# flags.net
KiCad netlist of a schematic drawn in EAGLE
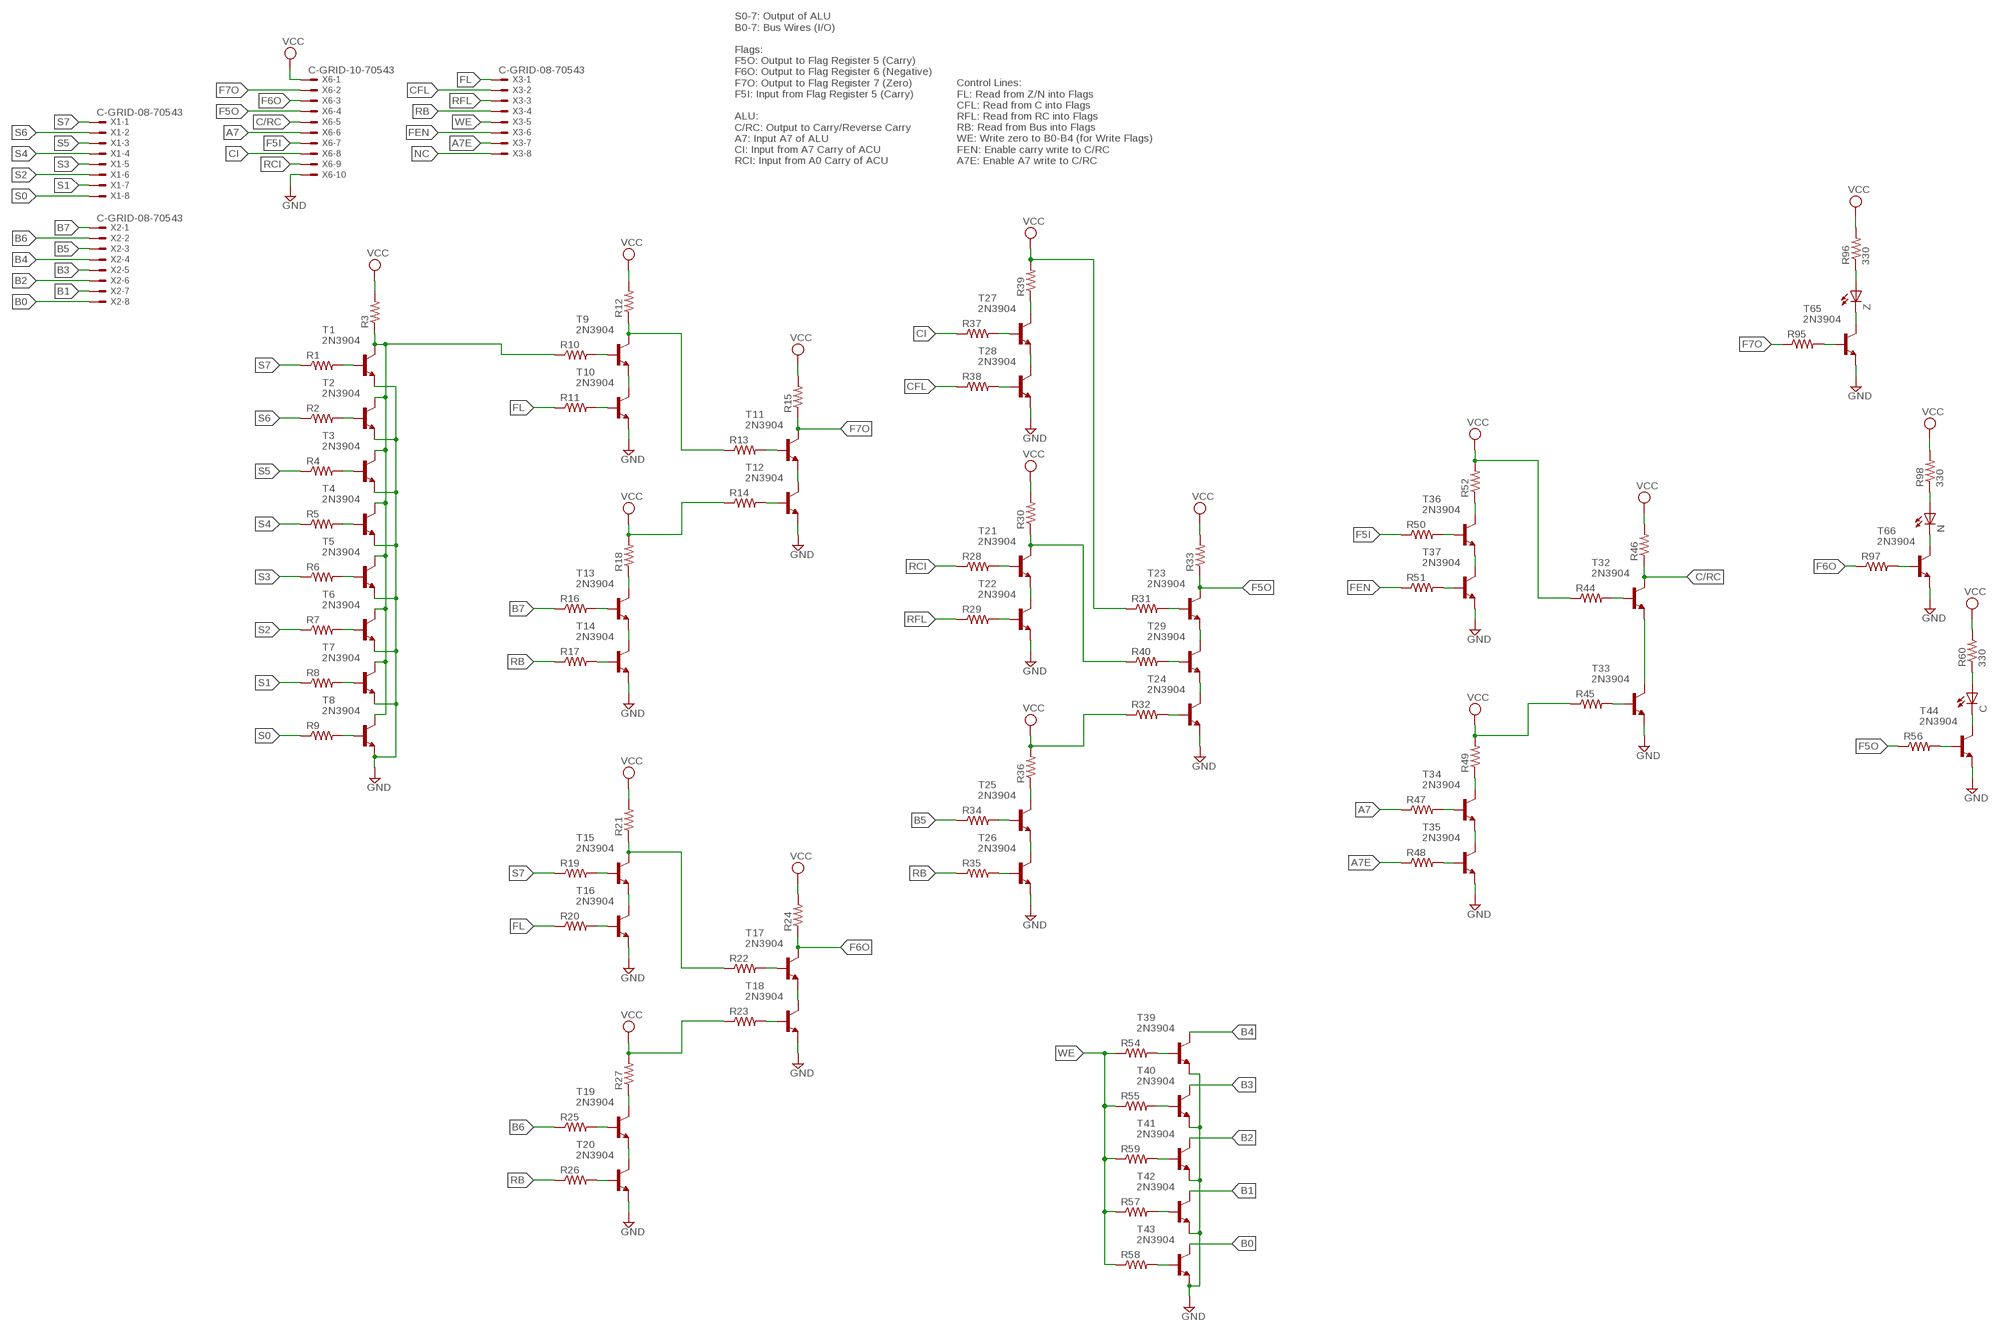
[diagram p0: schematic, sheet 1]

(export (version "E")
  (design (tool "Eeschema 10.0.6"))
  (components
    (comp (ref "C")
      (value "LED5MM")
      (footprint "eagle-import:LED5MM")
      (libsource (lib "eagle-import") (part "LED5MM"))
    )
    (comp (ref "N")
      (value "LED5MM")
      (footprint "eagle-import:LED5MM")
      (libsource (lib "eagle-import") (part "LED5MM"))
    )
    (comp (ref "R1")
      (value "R-US_0309/10")
      (footprint "eagle-import:0309_10")
      (libsource (lib "eagle-import") (part "R-US_0309/10"))
    )
    (comp (ref "R2")
      (value "R-US_0309/10")
      (footprint "eagle-import:0309_10")
      (libsource (lib "eagle-import") (part "R-US_0309/10"))
    )
    (comp (ref "R3")
      (value "R-US_0309/10")
      (footprint "eagle-import:0309_10")
      (libsource (lib "eagle-import") (part "R-US_0309/10"))
    )
    (comp (ref "R4")
      (value "R-US_0309/10")
      (footprint "eagle-import:0309_10")
      (libsource (lib "eagle-import") (part "R-US_0309/10"))
    )
    (comp (ref "R5")
      (value "R-US_0309/10")
      (footprint "eagle-import:0309_10")
      (libsource (lib "eagle-import") (part "R-US_0309/10"))
    )
    (comp (ref "R6")
      (value "R-US_0309/10")
      (footprint "eagle-import:0309_10")
      (libsource (lib "eagle-import") (part "R-US_0309/10"))
    )
    (comp (ref "R7")
      (value "R-US_0309/10")
      (footprint "eagle-import:0309_10")
      (libsource (lib "eagle-import") (part "R-US_0309/10"))
    )
    (comp (ref "R8")
      (value "R-US_0309/10")
      (footprint "eagle-import:0309_10")
      (libsource (lib "eagle-import") (part "R-US_0309/10"))
    )
    (comp (ref "R9")
      (value "R-US_0309/10")
      (footprint "eagle-import:0309_10")
      (libsource (lib "eagle-import") (part "R-US_0309/10"))
    )
    (comp (ref "R10")
      (value "R-US_0309/10")
      (footprint "eagle-import:0309_10")
      (libsource (lib "eagle-import") (part "R-US_0309/10"))
    )
    (comp (ref "R11")
      (value "R-US_0309/10")
      (footprint "eagle-import:0309_10")
      (libsource (lib "eagle-import") (part "R-US_0309/10"))
    )
    (comp (ref "R12")
      (value "R-US_0309/10")
      (footprint "eagle-import:0309_10")
      (libsource (lib "eagle-import") (part "R-US_0309/10"))
    )
    (comp (ref "R13")
      (value "R-US_0309/10")
      (footprint "eagle-import:0309_10")
      (libsource (lib "eagle-import") (part "R-US_0309/10"))
    )
    (comp (ref "R14")
      (value "R-US_0309/10")
      (footprint "eagle-import:0309_10")
      (libsource (lib "eagle-import") (part "R-US_0309/10"))
    )
    (comp (ref "R15")
      (value "R-US_0309/10")
      (footprint "eagle-import:0309_10")
      (libsource (lib "eagle-import") (part "R-US_0309/10"))
    )
    (comp (ref "R16")
      (value "R-US_0309/10")
      (footprint "eagle-import:0309_10")
      (libsource (lib "eagle-import") (part "R-US_0309/10"))
    )
    (comp (ref "R17")
      (value "R-US_0309/10")
      (footprint "eagle-import:0309_10")
      (libsource (lib "eagle-import") (part "R-US_0309/10"))
    )
    (comp (ref "R18")
      (value "R-US_0309/10")
      (footprint "eagle-import:0309_10")
      (libsource (lib "eagle-import") (part "R-US_0309/10"))
    )
    (comp (ref "R19")
      (value "R-US_0309/10")
      (footprint "eagle-import:0309_10")
      (libsource (lib "eagle-import") (part "R-US_0309/10"))
    )
    (comp (ref "R20")
      (value "R-US_0309/10")
      (footprint "eagle-import:0309_10")
      (libsource (lib "eagle-import") (part "R-US_0309/10"))
    )
    (comp (ref "R21")
      (value "R-US_0309/10")
      (footprint "eagle-import:0309_10")
      (libsource (lib "eagle-import") (part "R-US_0309/10"))
    )
    (comp (ref "R22")
      (value "R-US_0309/10")
      (footprint "eagle-import:0309_10")
      (libsource (lib "eagle-import") (part "R-US_0309/10"))
    )
    (comp (ref "R23")
      (value "R-US_0309/10")
      (footprint "eagle-import:0309_10")
      (libsource (lib "eagle-import") (part "R-US_0309/10"))
    )
    (comp (ref "R24")
      (value "R-US_0309/10")
      (footprint "eagle-import:0309_10")
      (libsource (lib "eagle-import") (part "R-US_0309/10"))
    )
    (comp (ref "R25")
      (value "R-US_0309/10")
      (footprint "eagle-import:0309_10")
      (libsource (lib "eagle-import") (part "R-US_0309/10"))
    )
    (comp (ref "R26")
      (value "R-US_0309/10")
      (footprint "eagle-import:0309_10")
      (libsource (lib "eagle-import") (part "R-US_0309/10"))
    )
    (comp (ref "R27")
      (value "R-US_0309/10")
      (footprint "eagle-import:0309_10")
      (libsource (lib "eagle-import") (part "R-US_0309/10"))
    )
    (comp (ref "R28")
      (value "R-US_0309/10")
      (footprint "eagle-import:0309_10")
      (libsource (lib "eagle-import") (part "R-US_0309/10"))
    )
    (comp (ref "R29")
      (value "R-US_0309/10")
      (footprint "eagle-import:0309_10")
      (libsource (lib "eagle-import") (part "R-US_0309/10"))
    )
    (comp (ref "R30")
      (value "R-US_0309/10")
      (footprint "eagle-import:0309_10")
      (libsource (lib "eagle-import") (part "R-US_0309/10"))
    )
    (comp (ref "R31")
      (value "R-US_0309/10")
      (footprint "eagle-import:0309_10")
      (libsource (lib "eagle-import") (part "R-US_0309/10"))
    )
    (comp (ref "R32")
      (value "R-US_0309/10")
      (footprint "eagle-import:0309_10")
      (libsource (lib "eagle-import") (part "R-US_0309/10"))
    )
    (comp (ref "R33")
      (value "R-US_0309/10")
      (footprint "eagle-import:0309_10")
      (libsource (lib "eagle-import") (part "R-US_0309/10"))
    )
    (comp (ref "R34")
      (value "R-US_0309/10")
      (footprint "eagle-import:0309_10")
      (libsource (lib "eagle-import") (part "R-US_0309/10"))
    )
    (comp (ref "R35")
      (value "R-US_0309/10")
      (footprint "eagle-import:0309_10")
      (libsource (lib "eagle-import") (part "R-US_0309/10"))
    )
    (comp (ref "R36")
      (value "R-US_0309/10")
      (footprint "eagle-import:0309_10")
      (libsource (lib "eagle-import") (part "R-US_0309/10"))
    )
    (comp (ref "R37")
      (value "R-US_0309/10")
      (footprint "eagle-import:0309_10")
      (libsource (lib "eagle-import") (part "R-US_0309/10"))
    )
    (comp (ref "R38")
      (value "R-US_0309/10")
      (footprint "eagle-import:0309_10")
      (libsource (lib "eagle-import") (part "R-US_0309/10"))
    )
    (comp (ref "R39")
      (value "R-US_0309/10")
      (footprint "eagle-import:0309_10")
      (libsource (lib "eagle-import") (part "R-US_0309/10"))
    )
    (comp (ref "R40")
      (value "R-US_0309/10")
      (footprint "eagle-import:0309_10")
      (libsource (lib "eagle-import") (part "R-US_0309/10"))
    )
    (comp (ref "R44")
      (value "R-US_0309/10")
      (footprint "eagle-import:0309_10")
      (libsource (lib "eagle-import") (part "R-US_0309/10"))
    )
    (comp (ref "R45")
      (value "R-US_0309/10")
      (footprint "eagle-import:0309_10")
      (libsource (lib "eagle-import") (part "R-US_0309/10"))
    )
    (comp (ref "R46")
      (value "R-US_0309/10")
      (footprint "eagle-import:0309_10")
      (libsource (lib "eagle-import") (part "R-US_0309/10"))
    )
    (comp (ref "R47")
      (value "R-US_0309/10")
      (footprint "eagle-import:0309_10")
      (libsource (lib "eagle-import") (part "R-US_0309/10"))
    )
    (comp (ref "R48")
      (value "R-US_0309/10")
      (footprint "eagle-import:0309_10")
      (libsource (lib "eagle-import") (part "R-US_0309/10"))
    )
    (comp (ref "R49")
      (value "R-US_0309/10")
      (footprint "eagle-import:0309_10")
      (libsource (lib "eagle-import") (part "R-US_0309/10"))
    )
    (comp (ref "R50")
      (value "R-US_0309/10")
      (footprint "eagle-import:0309_10")
      (libsource (lib "eagle-import") (part "R-US_0309/10"))
    )
    (comp (ref "R51")
      (value "R-US_0309/10")
      (footprint "eagle-import:0309_10")
      (libsource (lib "eagle-import") (part "R-US_0309/10"))
    )
    (comp (ref "R52")
      (value "R-US_0309/10")
      (footprint "eagle-import:0309_10")
      (libsource (lib "eagle-import") (part "R-US_0309/10"))
    )
    (comp (ref "R54")
      (value "R-US_0309/10")
      (footprint "eagle-import:0309_10")
      (libsource (lib "eagle-import") (part "R-US_0309/10"))
    )
    (comp (ref "R55")
      (value "R-US_0309/10")
      (footprint "eagle-import:0309_10")
      (libsource (lib "eagle-import") (part "R-US_0309/10"))
    )
    (comp (ref "R56")
      (value "R-US_0309/10")
      (footprint "eagle-import:0309_10")
      (libsource (lib "eagle-import") (part "R-US_0309/10"))
    )
    (comp (ref "R57")
      (value "R-US_0309/10")
      (footprint "eagle-import:0309_10")
      (libsource (lib "eagle-import") (part "R-US_0309/10"))
    )
    (comp (ref "R58")
      (value "R-US_0309/10")
      (footprint "eagle-import:0309_10")
      (libsource (lib "eagle-import") (part "R-US_0309/10"))
    )
    (comp (ref "R59")
      (value "R-US_0309/10")
      (footprint "eagle-import:0309_10")
      (libsource (lib "eagle-import") (part "R-US_0309/10"))
    )
    (comp (ref "R60")
      (value "330")
      (footprint "eagle-import:0309_10")
      (libsource (lib "eagle-import") (part "R-US_0309/10"))
    )
    (comp (ref "R95")
      (value "R-US_0309/10")
      (footprint "eagle-import:0309_10")
      (libsource (lib "eagle-import") (part "R-US_0309/10"))
    )
    (comp (ref "R96")
      (value "330")
      (footprint "eagle-import:0309_10")
      (libsource (lib "eagle-import") (part "R-US_0309/10"))
    )
    (comp (ref "R97")
      (value "R-US_0309/10")
      (footprint "eagle-import:0309_10")
      (libsource (lib "eagle-import") (part "R-US_0309/10"))
    )
    (comp (ref "R98")
      (value "330")
      (footprint "eagle-import:0309_10")
      (libsource (lib "eagle-import") (part "R-US_0309/10"))
    )
    (comp (ref "T1")
      (value "2N3904")
      (footprint "eagle-import:TO92")
      (libsource (lib "eagle-import") (part "2N3904"))
    )
    (comp (ref "T2")
      (value "2N3904")
      (footprint "eagle-import:TO92")
      (libsource (lib "eagle-import") (part "2N3904"))
    )
    (comp (ref "T3")
      (value "2N3904")
      (footprint "eagle-import:TO92")
      (libsource (lib "eagle-import") (part "2N3904"))
    )
    (comp (ref "T4")
      (value "2N3904")
      (footprint "eagle-import:TO92")
      (libsource (lib "eagle-import") (part "2N3904"))
    )
    (comp (ref "T5")
      (value "2N3904")
      (footprint "eagle-import:TO92")
      (libsource (lib "eagle-import") (part "2N3904"))
    )
    (comp (ref "T6")
      (value "2N3904")
      (footprint "eagle-import:TO92")
      (libsource (lib "eagle-import") (part "2N3904"))
    )
    (comp (ref "T7")
      (value "2N3904")
      (footprint "eagle-import:TO92")
      (libsource (lib "eagle-import") (part "2N3904"))
    )
    (comp (ref "T8")
      (value "2N3904")
      (footprint "eagle-import:TO92")
      (libsource (lib "eagle-import") (part "2N3904"))
    )
    (comp (ref "T9")
      (value "2N3904")
      (footprint "eagle-import:TO92")
      (libsource (lib "eagle-import") (part "2N3904"))
    )
    (comp (ref "T10")
      (value "2N3904")
      (footprint "eagle-import:TO92")
      (libsource (lib "eagle-import") (part "2N3904"))
    )
    (comp (ref "T11")
      (value "2N3904")
      (footprint "eagle-import:TO92")
      (libsource (lib "eagle-import") (part "2N3904"))
    )
    (comp (ref "T12")
      (value "2N3904")
      (footprint "eagle-import:TO92")
      (libsource (lib "eagle-import") (part "2N3904"))
    )
    (comp (ref "T13")
      (value "2N3904")
      (footprint "eagle-import:TO92")
      (libsource (lib "eagle-import") (part "2N3904"))
    )
    (comp (ref "T14")
      (value "2N3904")
      (footprint "eagle-import:TO92")
      (libsource (lib "eagle-import") (part "2N3904"))
    )
    (comp (ref "T15")
      (value "2N3904")
      (footprint "eagle-import:TO92")
      (libsource (lib "eagle-import") (part "2N3904"))
    )
    (comp (ref "T16")
      (value "2N3904")
      (footprint "eagle-import:TO92")
      (libsource (lib "eagle-import") (part "2N3904"))
    )
    (comp (ref "T17")
      (value "2N3904")
      (footprint "eagle-import:TO92")
      (libsource (lib "eagle-import") (part "2N3904"))
    )
    (comp (ref "T18")
      (value "2N3904")
      (footprint "eagle-import:TO92")
      (libsource (lib "eagle-import") (part "2N3904"))
    )
    (comp (ref "T19")
      (value "2N3904")
      (footprint "eagle-import:TO92")
      (libsource (lib "eagle-import") (part "2N3904"))
    )
    (comp (ref "T20")
      (value "2N3904")
      (footprint "eagle-import:TO92")
      (libsource (lib "eagle-import") (part "2N3904"))
    )
    (comp (ref "T21")
      (value "2N3904")
      (footprint "eagle-import:TO92")
      (libsource (lib "eagle-import") (part "2N3904"))
    )
    (comp (ref "T22")
      (value "2N3904")
      (footprint "eagle-import:TO92")
      (libsource (lib "eagle-import") (part "2N3904"))
    )
    (comp (ref "T23")
      (value "2N3904")
      (footprint "eagle-import:TO92")
      (libsource (lib "eagle-import") (part "2N3904"))
    )
    (comp (ref "T24")
      (value "2N3904")
      (footprint "eagle-import:TO92")
      (libsource (lib "eagle-import") (part "2N3904"))
    )
    (comp (ref "T25")
      (value "2N3904")
      (footprint "eagle-import:TO92")
      (libsource (lib "eagle-import") (part "2N3904"))
    )
    (comp (ref "T26")
      (value "2N3904")
      (footprint "eagle-import:TO92")
      (libsource (lib "eagle-import") (part "2N3904"))
    )
    (comp (ref "T27")
      (value "2N3904")
      (footprint "eagle-import:TO92")
      (libsource (lib "eagle-import") (part "2N3904"))
    )
    (comp (ref "T28")
      (value "2N3904")
      (footprint "eagle-import:TO92")
      (libsource (lib "eagle-import") (part "2N3904"))
    )
    (comp (ref "T29")
      (value "2N3904")
      (footprint "eagle-import:TO92")
      (libsource (lib "eagle-import") (part "2N3904"))
    )
    (comp (ref "T32")
      (value "2N3904")
      (footprint "eagle-import:TO92")
      (libsource (lib "eagle-import") (part "2N3904"))
    )
    (comp (ref "T33")
      (value "2N3904")
      (footprint "eagle-import:TO92")
      (libsource (lib "eagle-import") (part "2N3904"))
    )
    (comp (ref "T34")
      (value "2N3904")
      (footprint "eagle-import:TO92")
      (libsource (lib "eagle-import") (part "2N3904"))
    )
    (comp (ref "T35")
      (value "2N3904")
      (footprint "eagle-import:TO92")
      (libsource (lib "eagle-import") (part "2N3904"))
    )
    (comp (ref "T36")
      (value "2N3904")
      (footprint "eagle-import:TO92")
      (libsource (lib "eagle-import") (part "2N3904"))
    )
    (comp (ref "T37")
      (value "2N3904")
      (footprint "eagle-import:TO92")
      (libsource (lib "eagle-import") (part "2N3904"))
    )
    (comp (ref "T39")
      (value "2N3904")
      (footprint "eagle-import:TO92")
      (libsource (lib "eagle-import") (part "2N3904"))
    )
    (comp (ref "T40")
      (value "2N3904")
      (footprint "eagle-import:TO92")
      (libsource (lib "eagle-import") (part "2N3904"))
    )
    (comp (ref "T41")
      (value "2N3904")
      (footprint "eagle-import:TO92")
      (libsource (lib "eagle-import") (part "2N3904"))
    )
    (comp (ref "T42")
      (value "2N3904")
      (footprint "eagle-import:TO92")
      (libsource (lib "eagle-import") (part "2N3904"))
    )
    (comp (ref "T43")
      (value "2N3904")
      (footprint "eagle-import:TO92")
      (libsource (lib "eagle-import") (part "2N3904"))
    )
    (comp (ref "T44")
      (value "2N3904")
      (footprint "eagle-import:TO92")
      (libsource (lib "eagle-import") (part "2N3904"))
    )
    (comp (ref "T65")
      (value "2N3904")
      (footprint "eagle-import:TO92")
      (libsource (lib "eagle-import") (part "2N3904"))
    )
    (comp (ref "T66")
      (value "2N3904")
      (footprint "eagle-import:TO92")
      (libsource (lib "eagle-import") (part "2N3904"))
    )
    (comp (ref "X1")
      (value "C-GRID-08-70543")
      (footprint "eagle-import:70543-08")
      (fields (field (name "MF") "MOLEX"))
      (libsource (lib "eagle-import") (part "C-GRID-08-70543"))
    )
    (comp (ref "X2")
      (value "C-GRID-08-70543")
      (footprint "eagle-import:70543-08")
      (fields (field (name "MF") "MOLEX"))
      (libsource (lib "eagle-import") (part "C-GRID-08-70543"))
    )
    (comp (ref "X3")
      (value "C-GRID-08-70543")
      (footprint "eagle-import:70543-08")
      (fields (field (name "MF") "MOLEX"))
      (libsource (lib "eagle-import") (part "C-GRID-08-70543"))
    )
    (comp (ref "X6")
      (value "C-GRID-10-70543")
      (footprint "eagle-import:70543-10")
      (fields (field (name "MF") "MOLEX"))
      (libsource (lib "eagle-import") (part "C-GRID-10-70543"))
    )
    (comp (ref "Z")
      (value "LED5MM")
      (footprint "eagle-import:LED5MM")
      (libsource (lib "eagle-import") (part "LED5MM"))
    )
  )
  (nets
    (net (code "1") (name "A7") (class "Default")
      (node (ref "R47") (pin "1") (pinfunction "1_1") (pintype "passive"))
      (node (ref "X6") (pin "6") (pinfunction "S_6") (pintype "passive"))
    )
    (net (code "2") (name "A7E") (class "Default")
      (node (ref "R48") (pin "1") (pinfunction "1_1") (pintype "passive"))
      (node (ref "X3") (pin "7") (pinfunction "S_7") (pintype "passive"))
    )
    (net (code "3") (name "B0") (class "Default")
      (node (ref "T43") (pin "1") (pinfunction "C_1") (pintype "passive"))
      (node (ref "X2") (pin "8") (pinfunction "S_8") (pintype "passive"))
    )
    (net (code "4") (name "B1") (class "Default")
      (node (ref "T42") (pin "1") (pinfunction "C_1") (pintype "passive"))
      (node (ref "X2") (pin "7") (pinfunction "S_7") (pintype "passive"))
    )
    (net (code "5") (name "B2") (class "Default")
      (node (ref "T41") (pin "1") (pinfunction "C_1") (pintype "passive"))
      (node (ref "X2") (pin "6") (pinfunction "S_6") (pintype "passive"))
    )
    (net (code "6") (name "B3") (class "Default")
      (node (ref "T40") (pin "1") (pinfunction "C_1") (pintype "passive"))
      (node (ref "X2") (pin "5") (pinfunction "S_5") (pintype "passive"))
    )
    (net (code "7") (name "B4") (class "Default")
      (node (ref "T39") (pin "1") (pinfunction "C_1") (pintype "passive"))
      (node (ref "X2") (pin "4") (pinfunction "S_4") (pintype "passive"))
    )
    (net (code "8") (name "B5") (class "Default")
      (node (ref "R34") (pin "1") (pinfunction "1_1") (pintype "passive"))
      (node (ref "X2") (pin "3") (pinfunction "S_3") (pintype "passive"))
    )
    (net (code "9") (name "B6") (class "Default")
      (node (ref "R25") (pin "1") (pinfunction "1_1") (pintype "passive"))
      (node (ref "X2") (pin "2") (pinfunction "S_2") (pintype "passive"))
    )
    (net (code "10") (name "B7") (class "Default")
      (node (ref "R16") (pin "1") (pinfunction "1_1") (pintype "passive"))
      (node (ref "X2") (pin "1") (pinfunction "S_1") (pintype "passive"))
    )
    (net (code "11") (name "CFL") (class "Default")
      (node (ref "R38") (pin "1") (pinfunction "1_1") (pintype "passive"))
      (node (ref "X3") (pin "2") (pinfunction "S_2") (pintype "passive"))
    )
    (net (code "12") (name "CI") (class "Default")
      (node (ref "R37") (pin "1") (pinfunction "1_1") (pintype "passive"))
      (node (ref "X6") (pin "8") (pinfunction "S_8") (pintype "passive"))
    )
    (net (code "13") (name "C{slash}RC") (class "Default")
      (node (ref "R46") (pin "1") (pinfunction "1_1") (pintype "passive"))
      (node (ref "T32") (pin "1") (pinfunction "C_1") (pintype "passive"))
      (node (ref "X6") (pin "5") (pinfunction "S_5") (pintype "passive"))
    )
    (net (code "14") (name "F5I") (class "Default")
      (node (ref "R50") (pin "1") (pinfunction "1_1") (pintype "passive"))
      (node (ref "X6") (pin "7") (pinfunction "S_7") (pintype "passive"))
    )
    (net (code "15") (name "F5O") (class "Default")
      (node (ref "R33") (pin "1") (pinfunction "1_1") (pintype "passive"))
      (node (ref "R56") (pin "1") (pinfunction "1_1") (pintype "passive"))
      (node (ref "T23") (pin "1") (pinfunction "C_1") (pintype "passive"))
      (node (ref "X6") (pin "4") (pinfunction "S_4") (pintype "passive"))
    )
    (net (code "16") (name "F6O") (class "Default")
      (node (ref "R24") (pin "1") (pinfunction "1_1") (pintype "passive"))
      (node (ref "R97") (pin "1") (pinfunction "1_1") (pintype "passive"))
      (node (ref "T17") (pin "1") (pinfunction "C_1") (pintype "passive"))
      (node (ref "X6") (pin "3") (pinfunction "S_3") (pintype "passive"))
    )
    (net (code "17") (name "F7O") (class "Default")
      (node (ref "R15") (pin "1") (pinfunction "1_1") (pintype "passive"))
      (node (ref "R95") (pin "1") (pinfunction "1_1") (pintype "passive"))
      (node (ref "T11") (pin "1") (pinfunction "C_1") (pintype "passive"))
      (node (ref "X6") (pin "2") (pinfunction "S_2") (pintype "passive"))
    )
    (net (code "18") (name "FEN") (class "Default")
      (node (ref "R51") (pin "1") (pinfunction "1_1") (pintype "passive"))
      (node (ref "X3") (pin "6") (pinfunction "S_6") (pintype "passive"))
    )
    (net (code "19") (name "FL") (class "Default")
      (node (ref "R11") (pin "1") (pinfunction "1_1") (pintype "passive"))
      (node (ref "R20") (pin "1") (pinfunction "1_1") (pintype "passive"))
      (node (ref "X3") (pin "1") (pinfunction "S_1") (pintype "passive"))
    )
    (net (code "20") (name "GND") (class "Default")
      (node (ref "T1") (pin "3") (pinfunction "E_3") (pintype "passive"))
      (node (ref "T10") (pin "3") (pinfunction "E_3") (pintype "passive"))
      (node (ref "T12") (pin "3") (pinfunction "E_3") (pintype "passive"))
      (node (ref "T14") (pin "3") (pinfunction "E_3") (pintype "passive"))
      (node (ref "T16") (pin "3") (pinfunction "E_3") (pintype "passive"))
      (node (ref "T18") (pin "3") (pinfunction "E_3") (pintype "passive"))
      (node (ref "T2") (pin "3") (pinfunction "E_3") (pintype "passive"))
      (node (ref "T20") (pin "3") (pinfunction "E_3") (pintype "passive"))
      (node (ref "T22") (pin "3") (pinfunction "E_3") (pintype "passive"))
      (node (ref "T24") (pin "3") (pinfunction "E_3") (pintype "passive"))
      (node (ref "T26") (pin "3") (pinfunction "E_3") (pintype "passive"))
      (node (ref "T28") (pin "3") (pinfunction "E_3") (pintype "passive"))
      (node (ref "T3") (pin "3") (pinfunction "E_3") (pintype "passive"))
      (node (ref "T33") (pin "3") (pinfunction "E_3") (pintype "passive"))
      (node (ref "T35") (pin "3") (pinfunction "E_3") (pintype "passive"))
      (node (ref "T37") (pin "3") (pinfunction "E_3") (pintype "passive"))
      (node (ref "T39") (pin "3") (pinfunction "E_3") (pintype "passive"))
      (node (ref "T4") (pin "3") (pinfunction "E_3") (pintype "passive"))
      (node (ref "T40") (pin "3") (pinfunction "E_3") (pintype "passive"))
      (node (ref "T41") (pin "3") (pinfunction "E_3") (pintype "passive"))
      (node (ref "T42") (pin "3") (pinfunction "E_3") (pintype "passive"))
      (node (ref "T43") (pin "3") (pinfunction "E_3") (pintype "passive"))
      (node (ref "T44") (pin "3") (pinfunction "E_3") (pintype "passive"))
      (node (ref "T5") (pin "3") (pinfunction "E_3") (pintype "passive"))
      (node (ref "T6") (pin "3") (pinfunction "E_3") (pintype "passive"))
      (node (ref "T65") (pin "3") (pinfunction "E_3") (pintype "passive"))
      (node (ref "T66") (pin "3") (pinfunction "E_3") (pintype "passive"))
      (node (ref "T7") (pin "3") (pinfunction "E_3") (pintype "passive"))
      (node (ref "T8") (pin "3") (pinfunction "E_3") (pintype "passive"))
      (node (ref "X6") (pin "10") (pinfunction "S_10") (pintype "passive"))
    )
    (net (code "21") (name "NC") (class "Default")
      (node (ref "X3") (pin "8") (pinfunction "S_8") (pintype "passive"))
    )
    (net (code "22") (name "Net-(C-C)") (class "Default")
      (node (ref "C") (pin "K") (pinfunction "C_K") (pintype "passive"))
      (node (ref "T44") (pin "1") (pinfunction "C_1") (pintype "passive"))
    )
    (net (code "23") (name "Net-(C-PadA)") (class "Default")
      (node (ref "C") (pin "A") (pinfunction "A_A") (pintype "passive"))
      (node (ref "R60") (pin "1") (pinfunction "1_1") (pintype "passive"))
    )
    (net (code "24") (name "Net-(N-C)") (class "Default")
      (node (ref "N") (pin "K") (pinfunction "C_K") (pintype "passive"))
      (node (ref "T66") (pin "1") (pinfunction "C_1") (pintype "passive"))
    )
    (net (code "25") (name "Net-(N-PadA)") (class "Default")
      (node (ref "N") (pin "A") (pinfunction "A_A") (pintype "passive"))
      (node (ref "R98") (pin "1") (pinfunction "1_1") (pintype "passive"))
    )
    (net (code "26") (name "Net-(R96-Pad1)") (class "Default")
      (node (ref "R96") (pin "1") (pinfunction "1_1") (pintype "passive"))
      (node (ref "Z") (pin "A") (pinfunction "A_A") (pintype "passive"))
    )
    (net (code "27") (name "Net-(T1-B)") (class "Default")
      (node (ref "R1") (pin "2") (pinfunction "2_2") (pintype "passive"))
      (node (ref "T1") (pin "2") (pinfunction "B_2") (pintype "passive"))
    )
    (net (code "28") (name "Net-(T1-C)") (class "Default")
      (node (ref "R10") (pin "1") (pinfunction "1_1") (pintype "passive"))
      (node (ref "R3") (pin "1") (pinfunction "1_1") (pintype "passive"))
      (node (ref "T1") (pin "1") (pinfunction "C_1") (pintype "passive"))
      (node (ref "T2") (pin "1") (pinfunction "C_1") (pintype "passive"))
      (node (ref "T3") (pin "1") (pinfunction "C_1") (pintype "passive"))
      (node (ref "T4") (pin "1") (pinfunction "C_1") (pintype "passive"))
      (node (ref "T5") (pin "1") (pinfunction "C_1") (pintype "passive"))
      (node (ref "T6") (pin "1") (pinfunction "C_1") (pintype "passive"))
      (node (ref "T7") (pin "1") (pinfunction "C_1") (pintype "passive"))
      (node (ref "T8") (pin "1") (pinfunction "C_1") (pintype "passive"))
    )
    (net (code "29") (name "Net-(T2-B)") (class "Default")
      (node (ref "R2") (pin "2") (pinfunction "2_2") (pintype "passive"))
      (node (ref "T2") (pin "2") (pinfunction "B_2") (pintype "passive"))
    )
    (net (code "30") (name "Net-(T3-B)") (class "Default")
      (node (ref "R4") (pin "2") (pinfunction "2_2") (pintype "passive"))
      (node (ref "T3") (pin "2") (pinfunction "B_2") (pintype "passive"))
    )
    (net (code "31") (name "Net-(T4-B)") (class "Default")
      (node (ref "R5") (pin "2") (pinfunction "2_2") (pintype "passive"))
      (node (ref "T4") (pin "2") (pinfunction "B_2") (pintype "passive"))
    )
    (net (code "32") (name "Net-(T5-B)") (class "Default")
      (node (ref "R6") (pin "2") (pinfunction "2_2") (pintype "passive"))
      (node (ref "T5") (pin "2") (pinfunction "B_2") (pintype "passive"))
    )
    (net (code "33") (name "Net-(T6-B)") (class "Default")
      (node (ref "R7") (pin "2") (pinfunction "2_2") (pintype "passive"))
      (node (ref "T6") (pin "2") (pinfunction "B_2") (pintype "passive"))
    )
    (net (code "34") (name "Net-(T7-B)") (class "Default")
      (node (ref "R8") (pin "2") (pinfunction "2_2") (pintype "passive"))
      (node (ref "T7") (pin "2") (pinfunction "B_2") (pintype "passive"))
    )
    (net (code "35") (name "Net-(T8-B)") (class "Default")
      (node (ref "R9") (pin "2") (pinfunction "2_2") (pintype "passive"))
      (node (ref "T8") (pin "2") (pinfunction "B_2") (pintype "passive"))
    )
    (net (code "36") (name "Net-(T9-B)") (class "Default")
      (node (ref "R10") (pin "2") (pinfunction "2_2") (pintype "passive"))
      (node (ref "T9") (pin "2") (pinfunction "B_2") (pintype "passive"))
    )
    (net (code "37") (name "Net-(T9-C)") (class "Default")
      (node (ref "R12") (pin "1") (pinfunction "1_1") (pintype "passive"))
      (node (ref "R13") (pin "1") (pinfunction "1_1") (pintype "passive"))
      (node (ref "T9") (pin "1") (pinfunction "C_1") (pintype "passive"))
    )
    (net (code "38") (name "Net-(T10-B)") (class "Default")
      (node (ref "R11") (pin "2") (pinfunction "2_2") (pintype "passive"))
      (node (ref "T10") (pin "2") (pinfunction "B_2") (pintype "passive"))
    )
    (net (code "39") (name "Net-(T10-C)") (class "Default")
      (node (ref "T10") (pin "1") (pinfunction "C_1") (pintype "passive"))
      (node (ref "T9") (pin "3") (pinfunction "E_3") (pintype "passive"))
    )
    (net (code "40") (name "Net-(T11-B)") (class "Default")
      (node (ref "R13") (pin "2") (pinfunction "2_2") (pintype "passive"))
      (node (ref "T11") (pin "2") (pinfunction "B_2") (pintype "passive"))
    )
    (net (code "41") (name "Net-(T11-E)") (class "Default")
      (node (ref "T11") (pin "3") (pinfunction "E_3") (pintype "passive"))
      (node (ref "T12") (pin "1") (pinfunction "C_1") (pintype "passive"))
    )
    (net (code "42") (name "Net-(T12-B)") (class "Default")
      (node (ref "R14") (pin "2") (pinfunction "2_2") (pintype "passive"))
      (node (ref "T12") (pin "2") (pinfunction "B_2") (pintype "passive"))
    )
    (net (code "43") (name "Net-(T13-B)") (class "Default")
      (node (ref "R16") (pin "2") (pinfunction "2_2") (pintype "passive"))
      (node (ref "T13") (pin "2") (pinfunction "B_2") (pintype "passive"))
    )
    (net (code "44") (name "Net-(T13-C)") (class "Default")
      (node (ref "R18") (pin "1") (pinfunction "1_1") (pintype "passive"))
      (node (ref "T13") (pin "1") (pinfunction "C_1") (pintype "passive"))
    )
    (net (code "45") (name "Net-(T13-E)") (class "Default")
      (node (ref "T13") (pin "3") (pinfunction "E_3") (pintype "passive"))
      (node (ref "T14") (pin "1") (pinfunction "C_1") (pintype "passive"))
    )
    (net (code "46") (name "Net-(T14-B)") (class "Default")
      (node (ref "R17") (pin "2") (pinfunction "2_2") (pintype "passive"))
      (node (ref "T14") (pin "2") (pinfunction "B_2") (pintype "passive"))
    )
    (net (code "47") (name "Net-(T15-B)") (class "Default")
      (node (ref "R19") (pin "2") (pinfunction "2_2") (pintype "passive"))
      (node (ref "T15") (pin "2") (pinfunction "B_2") (pintype "passive"))
    )
    (net (code "48") (name "Net-(T15-C)") (class "Default")
      (node (ref "R21") (pin "1") (pinfunction "1_1") (pintype "passive"))
      (node (ref "R22") (pin "1") (pinfunction "1_1") (pintype "passive"))
      (node (ref "T15") (pin "1") (pinfunction "C_1") (pintype "passive"))
    )
    (net (code "49") (name "Net-(T15-E)") (class "Default")
      (node (ref "T15") (pin "3") (pinfunction "E_3") (pintype "passive"))
      (node (ref "T16") (pin "1") (pinfunction "C_1") (pintype "passive"))
    )
    (net (code "50") (name "Net-(T16-B)") (class "Default")
      (node (ref "R20") (pin "2") (pinfunction "2_2") (pintype "passive"))
      (node (ref "T16") (pin "2") (pinfunction "B_2") (pintype "passive"))
    )
    (net (code "51") (name "Net-(T17-B)") (class "Default")
      (node (ref "R22") (pin "2") (pinfunction "2_2") (pintype "passive"))
      (node (ref "T17") (pin "2") (pinfunction "B_2") (pintype "passive"))
    )
    (net (code "52") (name "Net-(T17-E)") (class "Default")
      (node (ref "T17") (pin "3") (pinfunction "E_3") (pintype "passive"))
      (node (ref "T18") (pin "1") (pinfunction "C_1") (pintype "passive"))
    )
    (net (code "53") (name "Net-(T18-B)") (class "Default")
      (node (ref "R23") (pin "2") (pinfunction "2_2") (pintype "passive"))
      (node (ref "T18") (pin "2") (pinfunction "B_2") (pintype "passive"))
    )
    (net (code "54") (name "Net-(T19-B)") (class "Default")
      (node (ref "R25") (pin "2") (pinfunction "2_2") (pintype "passive"))
      (node (ref "T19") (pin "2") (pinfunction "B_2") (pintype "passive"))
    )
    (net (code "55") (name "Net-(T19-C)") (class "Default")
      (node (ref "R27") (pin "1") (pinfunction "1_1") (pintype "passive"))
      (node (ref "T19") (pin "1") (pinfunction "C_1") (pintype "passive"))
    )
    (net (code "56") (name "Net-(T19-E)") (class "Default")
      (node (ref "T19") (pin "3") (pinfunction "E_3") (pintype "passive"))
      (node (ref "T20") (pin "1") (pinfunction "C_1") (pintype "passive"))
    )
    (net (code "57") (name "Net-(T20-B)") (class "Default")
      (node (ref "R26") (pin "2") (pinfunction "2_2") (pintype "passive"))
      (node (ref "T20") (pin "2") (pinfunction "B_2") (pintype "passive"))
    )
    (net (code "58") (name "Net-(T21-B)") (class "Default")
      (node (ref "R28") (pin "2") (pinfunction "2_2") (pintype "passive"))
      (node (ref "T21") (pin "2") (pinfunction "B_2") (pintype "passive"))
    )
    (net (code "59") (name "Net-(T21-C)") (class "Default")
      (node (ref "R30") (pin "1") (pinfunction "1_1") (pintype "passive"))
      (node (ref "R40") (pin "1") (pinfunction "1_1") (pintype "passive"))
      (node (ref "T21") (pin "1") (pinfunction "C_1") (pintype "passive"))
    )
    (net (code "60") (name "Net-(T21-E)") (class "Default")
      (node (ref "T21") (pin "3") (pinfunction "E_3") (pintype "passive"))
      (node (ref "T22") (pin "1") (pinfunction "C_1") (pintype "passive"))
    )
    (net (code "61") (name "Net-(T22-B)") (class "Default")
      (node (ref "R29") (pin "2") (pinfunction "2_2") (pintype "passive"))
      (node (ref "T22") (pin "2") (pinfunction "B_2") (pintype "passive"))
    )
    (net (code "62") (name "Net-(T23-B)") (class "Default")
      (node (ref "R31") (pin "2") (pinfunction "2_2") (pintype "passive"))
      (node (ref "T23") (pin "2") (pinfunction "B_2") (pintype "passive"))
    )
    (net (code "63") (name "Net-(T23-E)") (class "Default")
      (node (ref "T23") (pin "3") (pinfunction "E_3") (pintype "passive"))
      (node (ref "T29") (pin "1") (pinfunction "C_1") (pintype "passive"))
    )
    (net (code "64") (name "Net-(T24-B)") (class "Default")
      (node (ref "R32") (pin "2") (pinfunction "2_2") (pintype "passive"))
      (node (ref "T24") (pin "2") (pinfunction "B_2") (pintype "passive"))
    )
    (net (code "65") (name "Net-(T24-C)") (class "Default")
      (node (ref "T24") (pin "1") (pinfunction "C_1") (pintype "passive"))
      (node (ref "T29") (pin "3") (pinfunction "E_3") (pintype "passive"))
    )
    (net (code "66") (name "Net-(T25-B)") (class "Default")
      (node (ref "R34") (pin "2") (pinfunction "2_2") (pintype "passive"))
      (node (ref "T25") (pin "2") (pinfunction "B_2") (pintype "passive"))
    )
    (net (code "67") (name "Net-(T25-C)") (class "Default")
      (node (ref "R36") (pin "1") (pinfunction "1_1") (pintype "passive"))
      (node (ref "T25") (pin "1") (pinfunction "C_1") (pintype "passive"))
    )
    (net (code "68") (name "Net-(T25-E)") (class "Default")
      (node (ref "T25") (pin "3") (pinfunction "E_3") (pintype "passive"))
      (node (ref "T26") (pin "1") (pinfunction "C_1") (pintype "passive"))
    )
    (net (code "69") (name "Net-(T26-B)") (class "Default")
      (node (ref "R35") (pin "2") (pinfunction "2_2") (pintype "passive"))
      (node (ref "T26") (pin "2") (pinfunction "B_2") (pintype "passive"))
    )
    (net (code "70") (name "Net-(T27-B)") (class "Default")
      (node (ref "R37") (pin "2") (pinfunction "2_2") (pintype "passive"))
      (node (ref "T27") (pin "2") (pinfunction "B_2") (pintype "passive"))
    )
    (net (code "71") (name "Net-(T27-C)") (class "Default")
      (node (ref "R39") (pin "1") (pinfunction "1_1") (pintype "passive"))
      (node (ref "T27") (pin "1") (pinfunction "C_1") (pintype "passive"))
    )
    (net (code "72") (name "Net-(T27-E)") (class "Default")
      (node (ref "T27") (pin "3") (pinfunction "E_3") (pintype "passive"))
      (node (ref "T28") (pin "1") (pinfunction "C_1") (pintype "passive"))
    )
    (net (code "73") (name "Net-(T28-B)") (class "Default")
      (node (ref "R38") (pin "2") (pinfunction "2_2") (pintype "passive"))
      (node (ref "T28") (pin "2") (pinfunction "B_2") (pintype "passive"))
    )
    (net (code "74") (name "Net-(T29-B)") (class "Default")
      (node (ref "R40") (pin "2") (pinfunction "2_2") (pintype "passive"))
      (node (ref "T29") (pin "2") (pinfunction "B_2") (pintype "passive"))
    )
    (net (code "75") (name "Net-(T32-B)") (class "Default")
      (node (ref "R44") (pin "2") (pinfunction "2_2") (pintype "passive"))
      (node (ref "T32") (pin "2") (pinfunction "B_2") (pintype "passive"))
    )
    (net (code "76") (name "Net-(T32-E)") (class "Default")
      (node (ref "T32") (pin "3") (pinfunction "E_3") (pintype "passive"))
      (node (ref "T33") (pin "1") (pinfunction "C_1") (pintype "passive"))
    )
    (net (code "77") (name "Net-(T33-B)") (class "Default")
      (node (ref "R45") (pin "2") (pinfunction "2_2") (pintype "passive"))
      (node (ref "T33") (pin "2") (pinfunction "B_2") (pintype "passive"))
    )
    (net (code "78") (name "Net-(T34-B)") (class "Default")
      (node (ref "R47") (pin "2") (pinfunction "2_2") (pintype "passive"))
      (node (ref "T34") (pin "2") (pinfunction "B_2") (pintype "passive"))
    )
    (net (code "79") (name "Net-(T34-C)") (class "Default")
      (node (ref "R49") (pin "1") (pinfunction "1_1") (pintype "passive"))
      (node (ref "T34") (pin "1") (pinfunction "C_1") (pintype "passive"))
    )
    (net (code "80") (name "Net-(T34-E)") (class "Default")
      (node (ref "T34") (pin "3") (pinfunction "E_3") (pintype "passive"))
      (node (ref "T35") (pin "1") (pinfunction "C_1") (pintype "passive"))
    )
    (net (code "81") (name "Net-(T35-B)") (class "Default")
      (node (ref "R48") (pin "2") (pinfunction "2_2") (pintype "passive"))
      (node (ref "T35") (pin "2") (pinfunction "B_2") (pintype "passive"))
    )
    (net (code "82") (name "Net-(T36-B)") (class "Default")
      (node (ref "R50") (pin "2") (pinfunction "2_2") (pintype "passive"))
      (node (ref "T36") (pin "2") (pinfunction "B_2") (pintype "passive"))
    )
    (net (code "83") (name "Net-(T36-C)") (class "Default")
      (node (ref "R52") (pin "1") (pinfunction "1_1") (pintype "passive"))
      (node (ref "T36") (pin "1") (pinfunction "C_1") (pintype "passive"))
    )
    (net (code "84") (name "Net-(T36-E)") (class "Default")
      (node (ref "T36") (pin "3") (pinfunction "E_3") (pintype "passive"))
      (node (ref "T37") (pin "1") (pinfunction "C_1") (pintype "passive"))
    )
    (net (code "85") (name "Net-(T37-B)") (class "Default")
      (node (ref "R51") (pin "2") (pinfunction "2_2") (pintype "passive"))
      (node (ref "T37") (pin "2") (pinfunction "B_2") (pintype "passive"))
    )
    (net (code "86") (name "Net-(T39-B)") (class "Default")
      (node (ref "R54") (pin "2") (pinfunction "2_2") (pintype "passive"))
      (node (ref "T39") (pin "2") (pinfunction "B_2") (pintype "passive"))
    )
    (net (code "87") (name "Net-(T40-B)") (class "Default")
      (node (ref "R55") (pin "2") (pinfunction "2_2") (pintype "passive"))
      (node (ref "T40") (pin "2") (pinfunction "B_2") (pintype "passive"))
    )
    (net (code "88") (name "Net-(T41-B)") (class "Default")
      (node (ref "R59") (pin "2") (pinfunction "2_2") (pintype "passive"))
      (node (ref "T41") (pin "2") (pinfunction "B_2") (pintype "passive"))
    )
    (net (code "89") (name "Net-(T42-B)") (class "Default")
      (node (ref "R57") (pin "2") (pinfunction "2_2") (pintype "passive"))
      (node (ref "T42") (pin "2") (pinfunction "B_2") (pintype "passive"))
    )
    (net (code "90") (name "Net-(T43-B)") (class "Default")
      (node (ref "R58") (pin "2") (pinfunction "2_2") (pintype "passive"))
      (node (ref "T43") (pin "2") (pinfunction "B_2") (pintype "passive"))
    )
    (net (code "91") (name "Net-(T44-B)") (class "Default")
      (node (ref "R56") (pin "2") (pinfunction "2_2") (pintype "passive"))
      (node (ref "T44") (pin "2") (pinfunction "B_2") (pintype "passive"))
    )
    (net (code "92") (name "Net-(T65-B)") (class "Default")
      (node (ref "R95") (pin "2") (pinfunction "2_2") (pintype "passive"))
      (node (ref "T65") (pin "2") (pinfunction "B_2") (pintype "passive"))
    )
    (net (code "93") (name "Net-(T65-C)") (class "Default")
      (node (ref "T65") (pin "1") (pinfunction "C_1") (pintype "passive"))
      (node (ref "Z") (pin "K") (pinfunction "C_K") (pintype "passive"))
    )
    (net (code "94") (name "Net-(T66-B)") (class "Default")
      (node (ref "R97") (pin "2") (pinfunction "2_2") (pintype "passive"))
      (node (ref "T66") (pin "2") (pinfunction "B_2") (pintype "passive"))
    )
    (net (code "95") (name "RB") (class "Default")
      (node (ref "R17") (pin "1") (pinfunction "1_1") (pintype "passive"))
      (node (ref "R26") (pin "1") (pinfunction "1_1") (pintype "passive"))
      (node (ref "R35") (pin "1") (pinfunction "1_1") (pintype "passive"))
      (node (ref "X3") (pin "4") (pinfunction "S_4") (pintype "passive"))
    )
    (net (code "96") (name "RCI") (class "Default")
      (node (ref "R28") (pin "1") (pinfunction "1_1") (pintype "passive"))
      (node (ref "X6") (pin "9") (pinfunction "S_9") (pintype "passive"))
    )
    (net (code "97") (name "RFL") (class "Default")
      (node (ref "R29") (pin "1") (pinfunction "1_1") (pintype "passive"))
      (node (ref "X3") (pin "3") (pinfunction "S_3") (pintype "passive"))
    )
    (net (code "98") (name "S0") (class "Default")
      (node (ref "R9") (pin "1") (pinfunction "1_1") (pintype "passive"))
      (node (ref "X1") (pin "8") (pinfunction "S_8") (pintype "passive"))
    )
    (net (code "99") (name "S1") (class "Default")
      (node (ref "R8") (pin "1") (pinfunction "1_1") (pintype "passive"))
      (node (ref "X1") (pin "7") (pinfunction "S_7") (pintype "passive"))
    )
    (net (code "100") (name "S2") (class "Default")
      (node (ref "R7") (pin "1") (pinfunction "1_1") (pintype "passive"))
      (node (ref "X1") (pin "6") (pinfunction "S_6") (pintype "passive"))
    )
    (net (code "101") (name "S3") (class "Default")
      (node (ref "R6") (pin "1") (pinfunction "1_1") (pintype "passive"))
      (node (ref "X1") (pin "5") (pinfunction "S_5") (pintype "passive"))
    )
    (net (code "102") (name "S4") (class "Default")
      (node (ref "R5") (pin "1") (pinfunction "1_1") (pintype "passive"))
      (node (ref "X1") (pin "4") (pinfunction "S_4") (pintype "passive"))
    )
    (net (code "103") (name "S5") (class "Default")
      (node (ref "R4") (pin "1") (pinfunction "1_1") (pintype "passive"))
      (node (ref "X1") (pin "3") (pinfunction "S_3") (pintype "passive"))
    )
    (net (code "104") (name "S6") (class "Default")
      (node (ref "R2") (pin "1") (pinfunction "1_1") (pintype "passive"))
      (node (ref "X1") (pin "2") (pinfunction "S_2") (pintype "passive"))
    )
    (net (code "105") (name "S7") (class "Default")
      (node (ref "R1") (pin "1") (pinfunction "1_1") (pintype "passive"))
      (node (ref "R19") (pin "1") (pinfunction "1_1") (pintype "passive"))
      (node (ref "X1") (pin "1") (pinfunction "S_1") (pintype "passive"))
    )
    (net (code "106") (name "VCC") (class "Default")
      (node (ref "R12") (pin "2") (pinfunction "2_2") (pintype "passive"))
      (node (ref "R14") (pin "1") (pinfunction "1_1") (pintype "passive"))
      (node (ref "R15") (pin "2") (pinfunction "2_2") (pintype "passive"))
      (node (ref "R18") (pin "2") (pinfunction "2_2") (pintype "passive"))
      (node (ref "R21") (pin "2") (pinfunction "2_2") (pintype "passive"))
      (node (ref "R23") (pin "1") (pinfunction "1_1") (pintype "passive"))
      (node (ref "R24") (pin "2") (pinfunction "2_2") (pintype "passive"))
      (node (ref "R27") (pin "2") (pinfunction "2_2") (pintype "passive"))
      (node (ref "R3") (pin "2") (pinfunction "2_2") (pintype "passive"))
      (node (ref "R30") (pin "2") (pinfunction "2_2") (pintype "passive"))
      (node (ref "R31") (pin "1") (pinfunction "1_1") (pintype "passive"))
      (node (ref "R32") (pin "1") (pinfunction "1_1") (pintype "passive"))
      (node (ref "R33") (pin "2") (pinfunction "2_2") (pintype "passive"))
      (node (ref "R36") (pin "2") (pinfunction "2_2") (pintype "passive"))
      (node (ref "R39") (pin "2") (pinfunction "2_2") (pintype "passive"))
      (node (ref "R44") (pin "1") (pinfunction "1_1") (pintype "passive"))
      (node (ref "R45") (pin "1") (pinfunction "1_1") (pintype "passive"))
      (node (ref "R46") (pin "2") (pinfunction "2_2") (pintype "passive"))
      (node (ref "R49") (pin "2") (pinfunction "2_2") (pintype "passive"))
      (node (ref "R52") (pin "2") (pinfunction "2_2") (pintype "passive"))
      (node (ref "R60") (pin "2") (pinfunction "2_2") (pintype "passive"))
      (node (ref "R96") (pin "2") (pinfunction "2_2") (pintype "passive"))
      (node (ref "R98") (pin "2") (pinfunction "2_2") (pintype "passive"))
      (node (ref "X6") (pin "1") (pinfunction "S_1") (pintype "passive"))
    )
    (net (code "107") (name "WE") (class "Default")
      (node (ref "R54") (pin "1") (pinfunction "1_1") (pintype "passive"))
      (node (ref "R55") (pin "1") (pinfunction "1_1") (pintype "passive"))
      (node (ref "R57") (pin "1") (pinfunction "1_1") (pintype "passive"))
      (node (ref "R58") (pin "1") (pinfunction "1_1") (pintype "passive"))
      (node (ref "R59") (pin "1") (pinfunction "1_1") (pintype "passive"))
      (node (ref "X3") (pin "5") (pinfunction "S_5") (pintype "passive"))
    )
  )
)
